# sensor_node1.net
KiCad netlist of a schematic drawn in Altium Designer
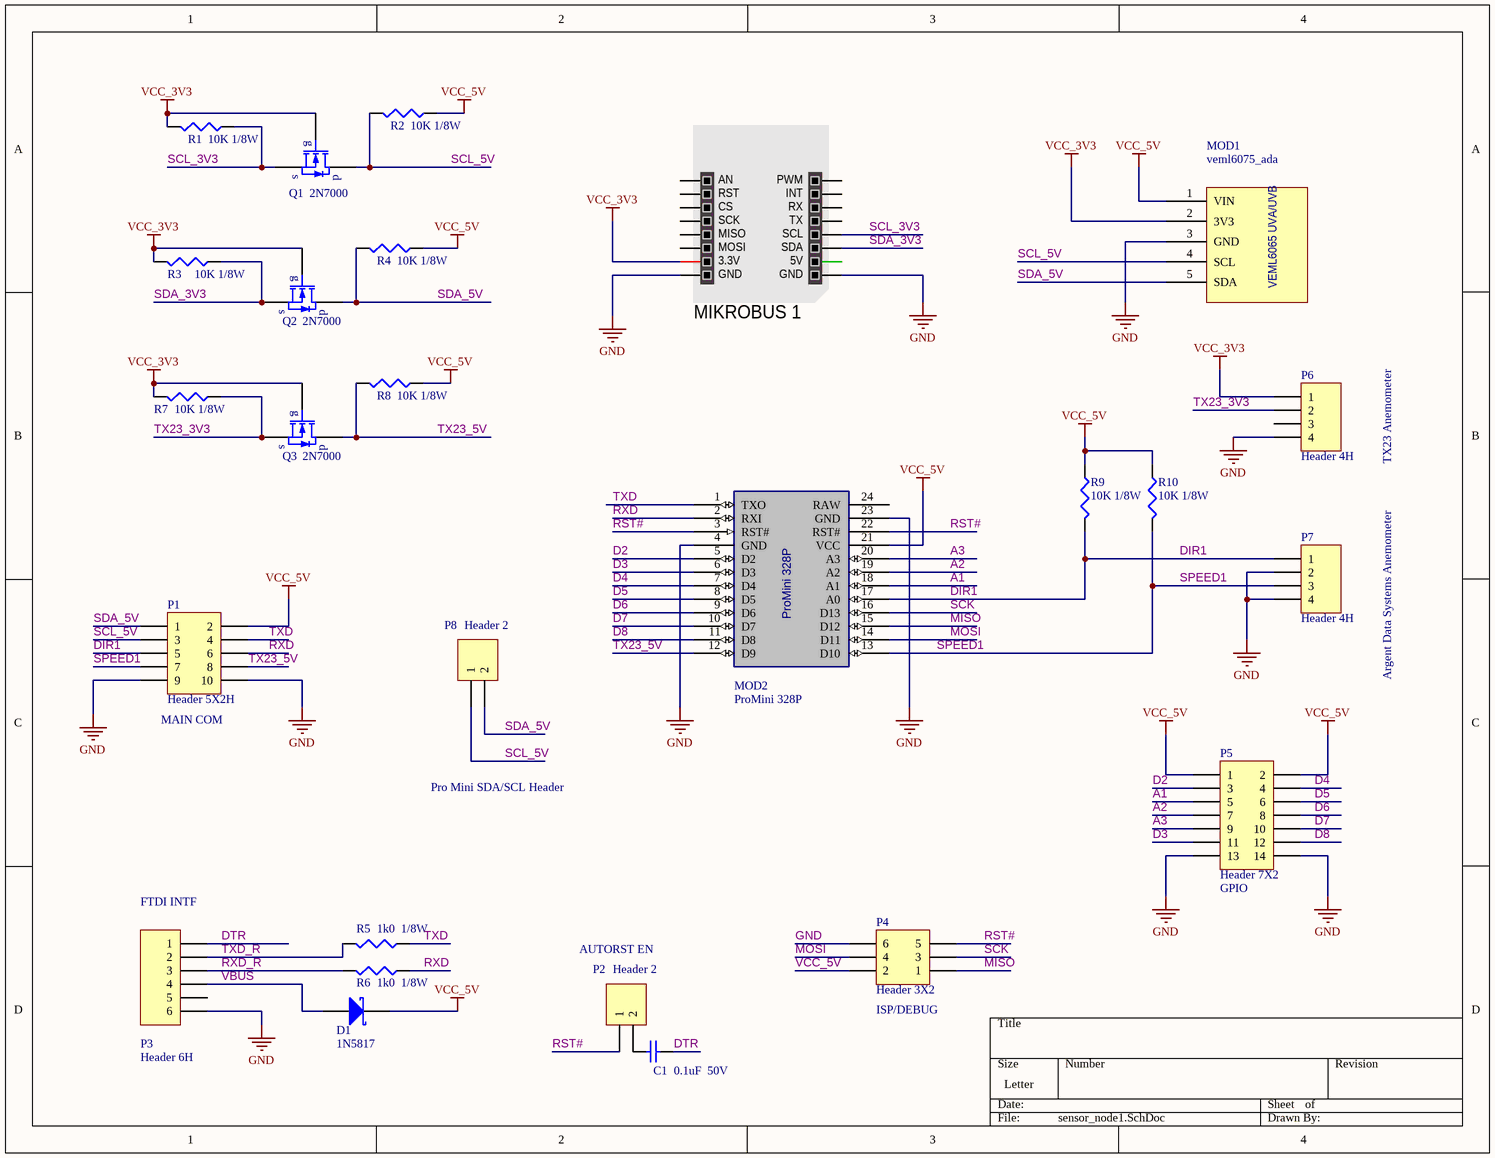
[diagram p0: sensor_node1.SchDoc]

(export (version "E")
  (design (tool "Eeschema 10.0.6"))
  (components
    (comp (ref "C1")
      (value "0.1uF  50V")
      (footprint "CAPR2.54-4x3.2")
      (fields
        (field (name "DIGI-KEY PART#") "BC1084CT-ND")
        (field (name "MANUFACTURER") "Vishay BC Components")
        (field (name "PARTNUMBER") "K104K15X7RF5TL2")
      )
      (libsource (lib "Miscellaneous Devices") (part "Cap"))
    )
    (comp (ref "D1")
      (value "1N5817")
      (footprint "DIODE-0.4")
      (fields
        (field (name "DIGI-KEY PART#") "1N5817-TPCT-ND")
        (field (name "MANUFACTURER") "Micro Commercial Co")
        (field (name "PARTNUMBER") "1N5817-TP")
      )
      (libsource (lib "mega328P_spider1") (part "D Schottky"))
    )
    (comp (ref "MIKROBUS 1")
      (value "MIKROBUS HOST CONN.")
      (footprint "MIKROBUS HOST CONN.")
      (description "mikroBUS Host Socket")
      (fields (field (name "DIGI-KEY PART#") "S7006-ND") (field (name "PARTNUMBER") "PPTC081LFBN-RC"))
      (libsource (lib "project_master") (part "MIKROBUS HOST CONN._1"))
    )
    (comp (ref "MOD1")
      (value "veml6075_ada")
      (footprint "HDR1X5")
      (libsource (lib "project_master") (part "veml6075_ada"))
    )
    (comp (ref "MOD2")
      (value "ProMini 328P")
      (footprint "promini")
      (fields
        (field (name "DIGI-KEY PART#") "S6100-ND")
        (field (name "MANUFACTURER") "Sullins")
        (field (name "PARTNUMBER") "PPTC051LFBN-RC")
      )
      (libsource (lib "demo_platforms") (part "promini_328P"))
    )
    (comp (ref "P1")
      (value "Header 5X2H")
      (footprint "HDR2X5H")
      (description "Header, 5-Pin, Dual row, Right Angle")
      (libsource (lib "Miscellaneous Connectors") (part "Header 5X2H"))
    )
    (comp (ref "P2")
      (value "Header 2")
      (footprint "HDR1X2")
      (libsource (lib "Miscellaneous Connectors") (part "Header 2"))
    )
    (comp (ref "P3")
      (value "Header 6H")
      (footprint "HDR1X6H")
      (libsource (lib "Miscellaneous Connectors") (part "Header 6H"))
    )
    (comp (ref "P4")
      (value "Header 3X2")
      (footprint "HDR2X3")
      (libsource (lib "Miscellaneous Connectors") (part "Header 3X2"))
    )
    (comp (ref "P5")
      (value "Header 7X2")
      (footprint "HDR2X7")
      (description "Header, 7-Pin, Dual row")
      (libsource (lib "Miscellaneous Connectors") (part "Header 7X2"))
    )
    (comp (ref "P6")
      (value "Header 4H")
      (footprint "HDR1X4H")
      (description "Header, 4-Pin, Right Angle")
      (libsource (lib "Miscellaneous Connectors") (part "Header 4H"))
    )
    (comp (ref "P7")
      (value "Header 4H")
      (footprint "HDR1X4H")
      (description "Header, 4-Pin, Right Angle")
      (libsource (lib "Miscellaneous Connectors") (part "Header 4H"))
    )
    (comp (ref "P8")
      (value "Header 2")
      (footprint "HDR1X2")
      (libsource (lib "Miscellaneous Connectors") (part "Header 2"))
    )
    (comp (ref "Q1")
      (value "2N7000")
      (footprint "2N7000-TO92")
      (description "2N7000 - TO92")
      (fields
        (field (name "DIGI-KEY PART#") "2N7000-G-ND")
        (field (name "MANUFACTURER") "Microchip Technology")
      )
      (libsource (lib "project_master") (part "2N7000"))
    )
    (comp (ref "Q2")
      (value "2N7000")
      (footprint "2N7000-TO92")
      (description "2N7000 - TO92")
      (fields
        (field (name "DIGI-KEY PART#") "2N7000-G-ND")
        (field (name "MANUFACTURER") "Microchip Technology")
      )
      (libsource (lib "project_master") (part "2N7000"))
    )
    (comp (ref "Q3")
      (value "2N7000")
      (footprint "2N7000-TO92")
      (description "2N7000 - TO92")
      (fields
        (field (name "DIGI-KEY PART#") "2N7000-G-ND")
        (field (name "MANUFACTURER") "Microchip Technology")
      )
      (libsource (lib "project_master") (part "2N7000"))
    )
    (comp (ref "R1")
      (value "10K 1/8W")
      (footprint "RES6.5-3.4X1.9")
      (description "Resistor")
      (fields (field (name "DIGI-KEY PART#") "CF18JT10K0CT-ND") (field (name "MANUFACTURER") "Stackpole"))
      (libsource (lib "Miscellaneous Devices") (part "Res3"))
    )
    (comp (ref "R2")
      (value "10K 1/8W")
      (footprint "RES6.5-3.4X1.9")
      (description "Resistor")
      (fields (field (name "DIGI-KEY PART#") "CF18JT10K0CT-ND") (field (name "MANUFACTURER") "Stackpole"))
      (libsource (lib "Miscellaneous Devices") (part "Res3"))
    )
    (comp (ref "R3")
      (value "10K 1/8W")
      (footprint "RES6.5-3.4X1.9")
      (description "Resistor")
      (fields (field (name "DIGI-KEY PART#") "CF18JT10K0CT-ND") (field (name "MANUFACTURER") "Stackpole"))
      (libsource (lib "Miscellaneous Devices") (part "Res3"))
    )
    (comp (ref "R4")
      (value "10K 1/8W")
      (footprint "RES6.5-3.4X1.9")
      (description "Resistor")
      (fields (field (name "DIGI-KEY PART#") "CF18JT10K0CT-ND") (field (name "MANUFACTURER") "Stackpole"))
      (libsource (lib "Miscellaneous Devices") (part "Res3"))
    )
    (comp (ref "R5")
      (value "1k0  1/8W")
      (footprint "RES6.5-3.4X1.9")
      (fields
        (field (name "DIGI-KEY PART#") "CF18JT1K00CT-ND")
        (field (name "MANUFACTURER") "Stackpole")
        (field (name "PARTNUMBER") "CF18JT1K00")
      )
      (libsource (lib "Miscellaneous Devices") (part "Res3"))
    )
    (comp (ref "R6")
      (value "1k0  1/8W")
      (footprint "RES6.5-3.4X1.9")
      (fields
        (field (name "DIGI-KEY PART#") "CF18JT1K00CT-ND")
        (field (name "MANUFACTURER") "Stackpole")
        (field (name "PARTNUMBER") "CF18JT1K00")
      )
      (libsource (lib "Miscellaneous Devices") (part "Res3"))
    )
    (comp (ref "R7")
      (value "10K 1/8W")
      (footprint "RES6.5-3.4X1.9")
      (description "Resistor")
      (fields (field (name "DIGI-KEY PART#") "CF18JT10K0CT-ND") (field (name "MANUFACTURER") "Stackpole"))
      (libsource (lib "Miscellaneous Devices") (part "Res3"))
    )
    (comp (ref "R8")
      (value "10K 1/8W")
      (footprint "RES6.5-3.4X1.9")
      (description "Resistor")
      (fields (field (name "DIGI-KEY PART#") "CF18JT10K0CT-ND") (field (name "MANUFACTURER") "Stackpole"))
      (libsource (lib "Miscellaneous Devices") (part "Res3"))
    )
    (comp (ref "R9")
      (value "10K 1/8W")
      (footprint "RES6.5-3.4X1.9")
      (description "Resistor")
      (fields (field (name "DIGI-KEY PART#") "CF18JT10K0CT-ND") (field (name "MANUFACTURER") "Stackpole"))
      (libsource (lib "Miscellaneous Devices") (part "Res3"))
    )
    (comp (ref "R10")
      (value "10K 1/8W")
      (footprint "RES6.5-3.4X1.9")
      (description "Resistor")
      (fields (field (name "DIGI-KEY PART#") "CF18JT10K0CT-ND") (field (name "MANUFACTURER") "Stackpole"))
      (libsource (lib "Miscellaneous Devices") (part "Res3"))
    )
  )
  (nets
    (net (code "1") (name "/A1") (class "Default")
      (node (ref "MOD2") (pin "18") (pinfunction "A1_18") (pintype "bidirectional"))
      (node (ref "P5") (pin "5") (pinfunction "5_5") (pintype "passive"))
    )
    (net (code "2") (name "/A2") (class "Default")
      (node (ref "MOD2") (pin "19") (pinfunction "A2_19") (pintype "bidirectional"))
      (node (ref "P5") (pin "7") (pinfunction "7_7") (pintype "passive"))
    )
    (net (code "3") (name "/A3") (class "Default")
      (node (ref "MOD2") (pin "20") (pinfunction "A3_20") (pintype "bidirectional"))
      (node (ref "P5") (pin "9") (pinfunction "9_9") (pintype "passive"))
    )
    (net (code "4") (name "/D2") (class "Default")
      (node (ref "MOD2") (pin "5") (pinfunction "D2_5") (pintype "bidirectional"))
      (node (ref "P5") (pin "3") (pinfunction "3_3") (pintype "passive"))
    )
    (net (code "5") (name "/D3") (class "Default")
      (node (ref "MOD2") (pin "6") (pinfunction "D3_6") (pintype "bidirectional"))
      (node (ref "P5") (pin "11") (pinfunction "11_11") (pintype "passive"))
    )
    (net (code "6") (name "/D4") (class "Default")
      (node (ref "MOD2") (pin "7") (pinfunction "D4_7") (pintype "bidirectional"))
      (node (ref "P5") (pin "4") (pinfunction "4_4") (pintype "passive"))
    )
    (net (code "7") (name "/D5") (class "Default")
      (node (ref "MOD2") (pin "8") (pinfunction "D5_8") (pintype "bidirectional"))
      (node (ref "P5") (pin "6") (pinfunction "6_6") (pintype "passive"))
    )
    (net (code "8") (name "/D6") (class "Default")
      (node (ref "MOD2") (pin "9") (pinfunction "D6_9") (pintype "bidirectional"))
      (node (ref "P5") (pin "8") (pinfunction "8_8") (pintype "passive"))
    )
    (net (code "9") (name "/D7") (class "Default")
      (node (ref "MOD2") (pin "10") (pinfunction "D7_10") (pintype "bidirectional"))
      (node (ref "P5") (pin "10") (pinfunction "10_10") (pintype "passive"))
    )
    (net (code "10") (name "/D8") (class "Default")
      (node (ref "MOD2") (pin "11") (pinfunction "D8_11") (pintype "bidirectional"))
      (node (ref "P5") (pin "12") (pinfunction "12_12") (pintype "passive"))
    )
    (net (code "11") (name "/DIR1") (class "Default")
      (node (ref "MOD2") (pin "17") (pinfunction "A0_17") (pintype "bidirectional"))
      (node (ref "P1") (pin "5") (pinfunction "5_5") (pintype "passive"))
      (node (ref "P7") (pin "1") (pinfunction "1_1") (pintype "passive"))
      (node (ref "R9") (pin "2") (pinfunction "2_2") (pintype "passive"))
    )
    (net (code "12") (name "/DTR") (class "Default")
      (node (ref "C1") (pin "1") (pinfunction "1_1") (pintype "passive"))
      (node (ref "P3") (pin "1") (pinfunction "1_1") (pintype "passive"))
    )
    (net (code "13") (name "/MISO") (class "Default")
      (node (ref "MOD2") (pin "15") (pinfunction "D12_15") (pintype "bidirectional"))
      (node (ref "P4") (pin "1") (pinfunction "1_1") (pintype "passive"))
    )
    (net (code "14") (name "/MOSI") (class "Default")
      (node (ref "MOD2") (pin "14") (pinfunction "D11_14") (pintype "bidirectional"))
      (node (ref "P4") (pin "4") (pinfunction "4_4") (pintype "passive"))
    )
    (net (code "15") (name "/RST#") (class "Default")
      (node (ref "MOD2") (pin "22") (pinfunction "RST#_22") (pintype "passive"))
      (node (ref "MOD2") (pin "3") (pinfunction "RST#_3") (pintype "input"))
      (node (ref "P2") (pin "1") (pinfunction "1_1") (pintype "passive"))
      (node (ref "P4") (pin "5") (pinfunction "5_5") (pintype "passive"))
    )
    (net (code "16") (name "/RXD") (class "Default")
      (node (ref "MOD2") (pin "2") (pinfunction "RXI_2") (pintype "bidirectional"))
      (node (ref "P1") (pin "6") (pinfunction "6_6") (pintype "passive"))
      (node (ref "R6") (pin "1") (pinfunction "1_1") (pintype "passive"))
    )
    (net (code "17") (name "/RXD_R") (class "Default")
      (node (ref "P3") (pin "3") (pinfunction "3_3") (pintype "passive"))
      (node (ref "R6") (pin "2") (pinfunction "2_2") (pintype "passive"))
    )
    (net (code "18") (name "/SCK") (class "Default")
      (node (ref "MOD2") (pin "16") (pinfunction "D13_16") (pintype "bidirectional"))
      (node (ref "P4") (pin "3") (pinfunction "3_3") (pintype "passive"))
    )
    (net (code "19") (name "/SCL_3V3") (class "Default")
      (node (ref "MIKROBUS 1") (pin "12") (pinfunction "SCL_12") (pintype "passive"))
      (node (ref "Q1") (pin "1") (pinfunction "S_1") (pintype "passive"))
      (node (ref "R1") (pin "1") (pinfunction "1_1") (pintype "passive"))
    )
    (net (code "20") (name "/SCL_5V") (class "Default")
      (node (ref "MOD1") (pin "4") (pinfunction "SCL_4") (pintype "passive"))
      (node (ref "P1") (pin "3") (pinfunction "3_3") (pintype "passive"))
      (node (ref "P8") (pin "1") (pinfunction "1_1") (pintype "passive"))
      (node (ref "Q1") (pin "3") (pinfunction "D_3") (pintype "passive"))
      (node (ref "R2") (pin "2") (pinfunction "2_2") (pintype "passive"))
    )
    (net (code "21") (name "/SDA_3V3") (class "Default")
      (node (ref "MIKROBUS 1") (pin "11") (pinfunction "SDA_11") (pintype "passive"))
      (node (ref "Q2") (pin "1") (pinfunction "S_1") (pintype "passive"))
      (node (ref "R3") (pin "1") (pinfunction "1_1") (pintype "passive"))
    )
    (net (code "22") (name "/SDA_5V") (class "Default")
      (node (ref "MOD1") (pin "5") (pinfunction "SDA_5") (pintype "passive"))
      (node (ref "P1") (pin "1") (pinfunction "1_1") (pintype "passive"))
      (node (ref "P8") (pin "2") (pinfunction "2_2") (pintype "passive"))
      (node (ref "Q2") (pin "3") (pinfunction "D_3") (pintype "passive"))
      (node (ref "R4") (pin "2") (pinfunction "2_2") (pintype "passive"))
    )
    (net (code "23") (name "/SPEED1") (class "Default")
      (node (ref "MOD2") (pin "13") (pinfunction "D10_13") (pintype "bidirectional"))
      (node (ref "P1") (pin "7") (pinfunction "7_7") (pintype "passive"))
      (node (ref "P7") (pin "3") (pinfunction "3_3") (pintype "passive"))
      (node (ref "R10") (pin "2") (pinfunction "2_2") (pintype "passive"))
    )
    (net (code "24") (name "/TX23_3V3") (class "Default")
      (node (ref "P6") (pin "2") (pinfunction "2_2") (pintype "passive"))
      (node (ref "Q3") (pin "1") (pinfunction "S_1") (pintype "passive"))
      (node (ref "R7") (pin "1") (pinfunction "1_1") (pintype "passive"))
    )
    (net (code "25") (name "/TX23_5V") (class "Default")
      (node (ref "MOD2") (pin "12") (pinfunction "D9_12") (pintype "bidirectional"))
      (node (ref "P1") (pin "8") (pinfunction "8_8") (pintype "passive"))
      (node (ref "Q3") (pin "3") (pinfunction "D_3") (pintype "passive"))
      (node (ref "R8") (pin "2") (pinfunction "2_2") (pintype "passive"))
    )
    (net (code "26") (name "/TXD") (class "Default")
      (node (ref "MOD2") (pin "1") (pinfunction "TXO_1") (pintype "bidirectional"))
      (node (ref "P1") (pin "4") (pinfunction "4_4") (pintype "passive"))
      (node (ref "R5") (pin "1") (pinfunction "1_1") (pintype "passive"))
    )
    (net (code "27") (name "/TXD_R") (class "Default")
      (node (ref "P3") (pin "2") (pinfunction "2_2") (pintype "passive"))
      (node (ref "R5") (pin "2") (pinfunction "2_2") (pintype "passive"))
    )
    (net (code "28") (name "/VBUS") (class "Default")
      (node (ref "D1") (pin "1") (pinfunction "A_1") (pintype "passive"))
      (node (ref "P3") (pin "4") (pinfunction "4_4") (pintype "passive"))
    )
    (net (code "29") (name "GND") (class "Default")
      (node (ref "MIKROBUS 1") (pin "8") (pinfunction "GND_8") (pintype "passive"))
      (node (ref "MIKROBUS 1") (pin "9") (pinfunction "GND_9") (pintype "passive"))
      (node (ref "MOD1") (pin "3") (pinfunction "GND_3") (pintype "passive"))
      (node (ref "MOD2") (pin "23") (pinfunction "GND_23") (pintype "passive"))
      (node (ref "MOD2") (pin "4") (pinfunction "GND_4") (pintype "passive"))
      (node (ref "P1") (pin "10") (pinfunction "10_10") (pintype "passive"))
      (node (ref "P1") (pin "9") (pinfunction "9_9") (pintype "passive"))
      (node (ref "P3") (pin "6") (pinfunction "6_6") (pintype "passive"))
      (node (ref "P4") (pin "6") (pinfunction "6_6") (pintype "passive"))
      (node (ref "P5") (pin "13") (pinfunction "13_13") (pintype "passive"))
      (node (ref "P5") (pin "14") (pinfunction "14_14") (pintype "passive"))
      (node (ref "P6") (pin "4") (pinfunction "4_4") (pintype "passive"))
      (node (ref "P7") (pin "2") (pinfunction "2_2") (pintype "passive"))
      (node (ref "P7") (pin "4") (pinfunction "4_4") (pintype "passive"))
    )
    (net (code "30") (name "Net-(C1-Pad2)") (class "Default")
      (node (ref "C1") (pin "2") (pinfunction "2_2") (pintype "passive"))
      (node (ref "P2") (pin "2") (pinfunction "2_2") (pintype "passive"))
    )
    (net (code "31") (name "VCC_3V3") (class "Default")
      (node (ref "MIKROBUS 1") (pin "7") (pinfunction "3.3V_7") (pintype "passive"))
      (node (ref "MOD1") (pin "2") (pinfunction "3V3_2") (pintype "passive"))
      (node (ref "P6") (pin "1") (pinfunction "1_1") (pintype "passive"))
      (node (ref "Q1") (pin "2") (pinfunction "G_2") (pintype "passive"))
      (node (ref "Q2") (pin "2") (pinfunction "G_2") (pintype "passive"))
      (node (ref "Q3") (pin "2") (pinfunction "G_2") (pintype "passive"))
      (node (ref "R1") (pin "2") (pinfunction "2_2") (pintype "passive"))
      (node (ref "R3") (pin "2") (pinfunction "2_2") (pintype "passive"))
      (node (ref "R7") (pin "2") (pinfunction "2_2") (pintype "passive"))
    )
    (net (code "32") (name "VCC_5V") (class "Default")
      (node (ref "D1") (pin "2") (pinfunction "K_2") (pintype "passive"))
      (node (ref "MOD1") (pin "1") (pinfunction "VIN_1") (pintype "passive"))
      (node (ref "MOD2") (pin "21") (pinfunction "VCC_21") (pintype "passive"))
      (node (ref "P1") (pin "2") (pinfunction "2_2") (pintype "passive"))
      (node (ref "P4") (pin "2") (pinfunction "2_2") (pintype "passive"))
      (node (ref "P5") (pin "1") (pinfunction "1_1") (pintype "passive"))
      (node (ref "P5") (pin "2") (pinfunction "2_2") (pintype "passive"))
      (node (ref "R10") (pin "1") (pinfunction "1_1") (pintype "passive"))
      (node (ref "R2") (pin "1") (pinfunction "1_1") (pintype "passive"))
      (node (ref "R4") (pin "1") (pinfunction "1_1") (pintype "passive"))
      (node (ref "R8") (pin "1") (pinfunction "1_1") (pintype "passive"))
      (node (ref "R9") (pin "1") (pinfunction "1_1") (pintype "passive"))
    )
    (net (code "33") (name "unconnected-(MIKROBUS 1-5V-Pad10)") (class "Default")
      (node (ref "MIKROBUS 1") (pin "10") (pinfunction "5V_10") (pintype "passive"))
    )
    (net (code "34") (name "unconnected-(MIKROBUS 1-AN-Pad1)") (class "Default")
      (node (ref "MIKROBUS 1") (pin "1") (pinfunction "AN_1") (pintype "passive"))
    )
    (net (code "35") (name "unconnected-(MIKROBUS 1-CS-Pad3)") (class "Default")
      (node (ref "MIKROBUS 1") (pin "3") (pinfunction "CS_3") (pintype "passive"))
    )
    (net (code "36") (name "unconnected-(MIKROBUS 1-INT-Pad15)") (class "Default")
      (node (ref "MIKROBUS 1") (pin "15") (pinfunction "INT_15") (pintype "passive"))
    )
    (net (code "37") (name "unconnected-(MIKROBUS 1-MISO-Pad5)") (class "Default")
      (node (ref "MIKROBUS 1") (pin "5") (pinfunction "MISO_5") (pintype "passive"))
    )
    (net (code "38") (name "unconnected-(MIKROBUS 1-MOSI-Pad6)") (class "Default")
      (node (ref "MIKROBUS 1") (pin "6") (pinfunction "MOSI_6") (pintype "passive"))
    )
    (net (code "39") (name "unconnected-(MIKROBUS 1-PWM-Pad16)") (class "Default")
      (node (ref "MIKROBUS 1") (pin "16") (pinfunction "PWM_16") (pintype "passive"))
    )
    (net (code "40") (name "unconnected-(MIKROBUS 1-RST-Pad2)") (class "Default")
      (node (ref "MIKROBUS 1") (pin "2") (pinfunction "RST_2") (pintype "passive"))
    )
    (net (code "41") (name "unconnected-(MIKROBUS 1-RX-Pad14)") (class "Default")
      (node (ref "MIKROBUS 1") (pin "14") (pinfunction "RX_14") (pintype "passive"))
    )
    (net (code "42") (name "unconnected-(MIKROBUS 1-SCK-Pad4)") (class "Default")
      (node (ref "MIKROBUS 1") (pin "4") (pinfunction "SCK_4") (pintype "passive"))
    )
    (net (code "43") (name "unconnected-(MIKROBUS 1-TX-Pad13)") (class "Default")
      (node (ref "MIKROBUS 1") (pin "13") (pinfunction "TX_13") (pintype "passive"))
    )
    (net (code "44") (name "unconnected-(MOD2-RAW-Pad24)") (class "Default")
      (node (ref "MOD2") (pin "24") (pinfunction "RAW_24") (pintype "passive"))
    )
    (net (code "45") (name "unconnected-(P3-Pad5)") (class "Default")
      (node (ref "P3") (pin "5") (pinfunction "5_5") (pintype "passive"))
    )
    (net (code "46") (name "unconnected-(P6-Pad3)") (class "Default")
      (node (ref "P6") (pin "3") (pinfunction "3_3") (pintype "passive"))
    )
  )
)
